# SuperClock_Core_PWR.net
KiCad netlist of a schematic drawn in Altium Designer
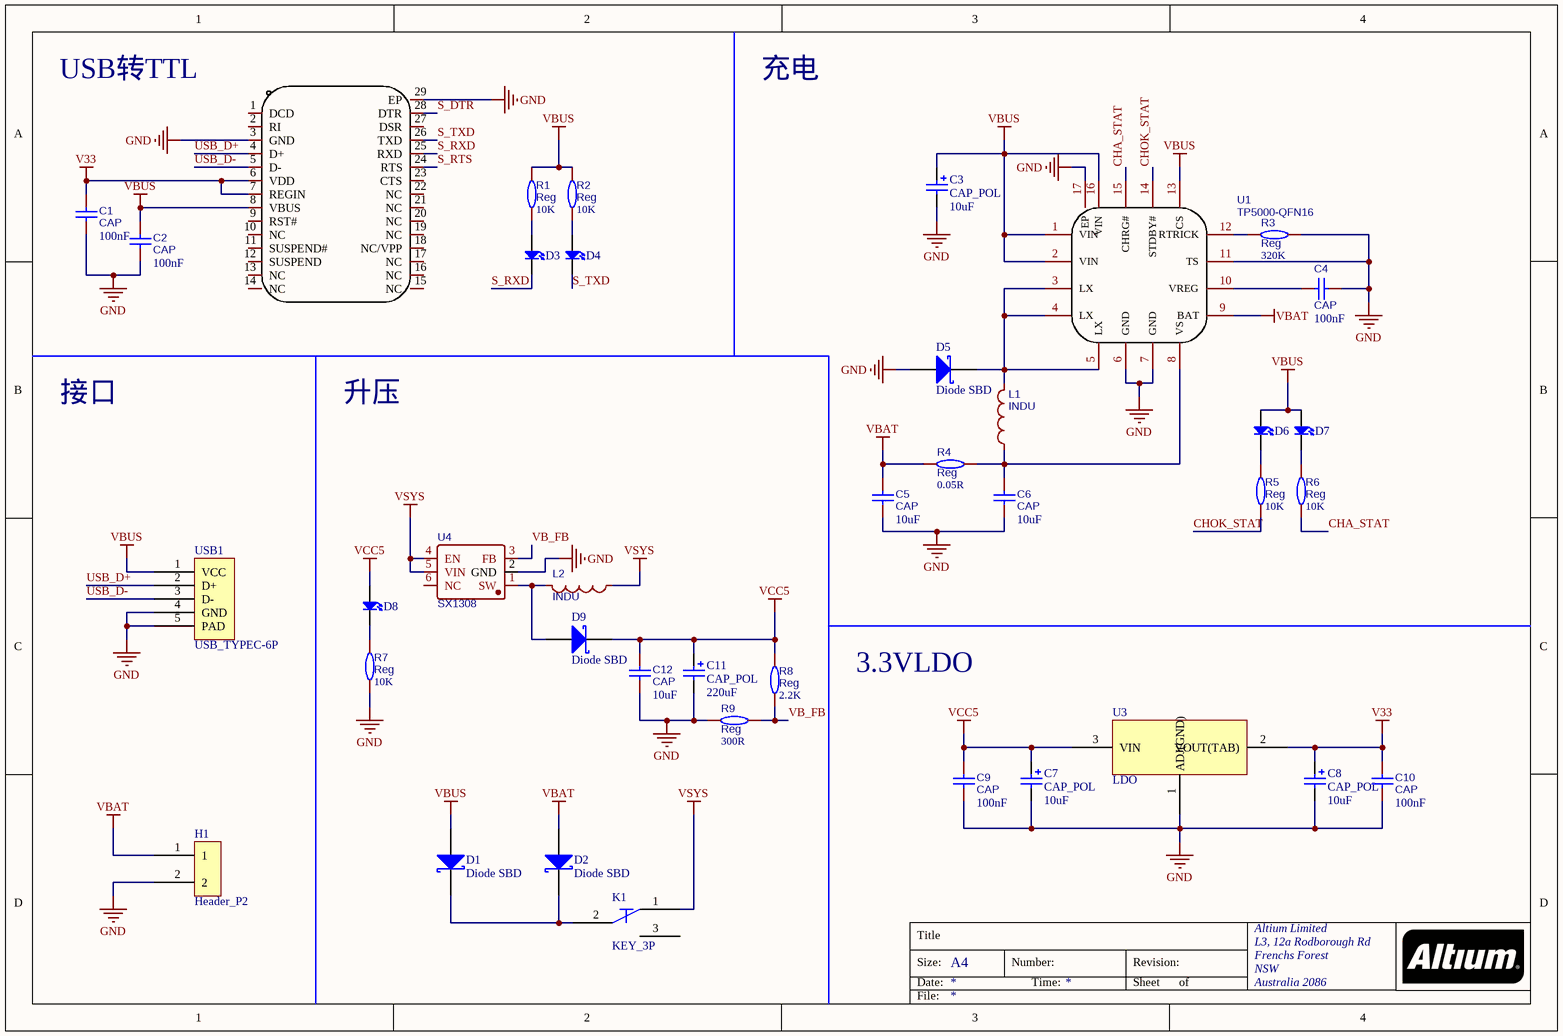
[diagram p0: SuperClock_Core_PWR.SchDoc]

(export (version "E")
  (design (tool "Eeschema 10.0.6"))
  (components
    (comp (ref "C1")
      (value "CAP")
      (footprint "C0603")
      (description "Cap")
      (fields
        (field (name "BOM_SUPPLIER PART") "C302008")
        (field (name "BOM_MANUFACTURER PART") "0603B103K101CT")
        (field (name "ALTIUM_VALUE") "100nF")
        (field (name "CONTRIBUTOR") "LCSC")
      )
      (libsource (lib "Levent_lib") (part "CAP"))
    )
    (comp (ref "C2")
      (value "CAP")
      (footprint "C0603")
      (description "Cap")
      (fields
        (field (name "BOM_SUPPLIER PART") "C302008")
        (field (name "BOM_MANUFACTURER PART") "0603B103K101CT")
        (field (name "ALTIUM_VALUE") "100nF")
        (field (name "CONTRIBUTOR") "LCSC")
      )
      (libsource (lib "Levent_lib") (part "CAP"))
    )
    (comp (ref "C3")
      (value "CAP_POL")
      (footprint "CP1206")
      (description "极性电容")
      (fields (field (name "ALTIUM_VALUE") "10uF"))
      (libsource (lib "Levent_lib") (part "CAP_POL"))
    )
    (comp (ref "C4")
      (value "CAP")
      (footprint "C0603")
      (description "Cap")
      (fields
        (field (name "BOM_SUPPLIER PART") "C302008")
        (field (name "BOM_MANUFACTURER PART") "0603B103K101CT")
        (field (name "ALTIUM_VALUE") "100nF")
        (field (name "CONTRIBUTOR") "LCSC")
      )
      (libsource (lib "Levent_lib") (part "CAP"))
    )
    (comp (ref "C5")
      (value "CAP")
      (footprint "C0603")
      (description "Cap")
      (fields
        (field (name "BOM_SUPPLIER PART") "C302008")
        (field (name "BOM_MANUFACTURER PART") "0603B103K101CT")
        (field (name "ALTIUM_VALUE") "10uF")
        (field (name "CONTRIBUTOR") "LCSC")
      )
      (libsource (lib "Levent_lib") (part "CAP"))
    )
    (comp (ref "C6")
      (value "CAP")
      (footprint "C0603")
      (description "Cap")
      (fields
        (field (name "BOM_SUPPLIER PART") "C302008")
        (field (name "BOM_MANUFACTURER PART") "0603B103K101CT")
        (field (name "ALTIUM_VALUE") "10uF")
        (field (name "CONTRIBUTOR") "LCSC")
      )
      (libsource (lib "Levent_lib") (part "CAP"))
    )
    (comp (ref "C7")
      (value "CAP_POL")
      (footprint "CP1206")
      (description "极性电容")
      (fields (field (name "ALTIUM_VALUE") "10uF"))
      (libsource (lib "Levent_lib") (part "CAP_POL"))
    )
    (comp (ref "C8")
      (value "CAP_POL")
      (footprint "CP1206")
      (description "极性电容")
      (fields (field (name "ALTIUM_VALUE") "10uF"))
      (libsource (lib "Levent_lib") (part "CAP_POL"))
    )
    (comp (ref "C9")
      (value "CAP")
      (footprint "C0603")
      (description "Cap")
      (fields
        (field (name "BOM_SUPPLIER PART") "C302008")
        (field (name "BOM_MANUFACTURER PART") "0603B103K101CT")
        (field (name "ALTIUM_VALUE") "100nF")
        (field (name "CONTRIBUTOR") "LCSC")
      )
      (libsource (lib "Levent_lib") (part "CAP"))
    )
    (comp (ref "C10")
      (value "CAP")
      (footprint "C0603")
      (description "Cap")
      (fields
        (field (name "BOM_SUPPLIER PART") "C302008")
        (field (name "BOM_MANUFACTURER PART") "0603B103K101CT")
        (field (name "ALTIUM_VALUE") "100nF")
        (field (name "CONTRIBUTOR") "LCSC")
      )
      (libsource (lib "Levent_lib") (part "CAP"))
    )
    (comp (ref "C11")
      (value "CAP_POL")
      (footprint "CAP_SMD_6.3mm")
      (description "极性电容")
      (fields (field (name "ALTIUM_VALUE") "220uF"))
      (libsource (lib "Levent_lib") (part "CAP_POL"))
    )
    (comp (ref "C12")
      (value "CAP")
      (footprint "C0603")
      (description "Cap")
      (fields
        (field (name "BOM_SUPPLIER PART") "C302008")
        (field (name "BOM_MANUFACTURER PART") "0603B103K101CT")
        (field (name "ALTIUM_VALUE") "10uF")
        (field (name "CONTRIBUTOR") "LCSC")
      )
      (libsource (lib "Levent_lib") (part "CAP"))
    )
    (comp (ref "D1")
      (value "Diode SBD")
      (footprint "SMA_L4.3")
      (description "Schottky Rectifier")
      (fields (field (name "PUBLISHER") "Altium Limited"))
      (libsource (lib "Levent_lib") (part "Diode SBD"))
    )
    (comp (ref "D2")
      (value "Diode SBD")
      (footprint "SMA_L4.3")
      (description "Schottky Rectifier")
      (fields (field (name "PUBLISHER") "Altium Limited"))
      (libsource (lib "Levent_lib") (part "Diode SBD"))
    )
    (comp (ref "D3")
      (value "LED")
      (footprint "LED0603")
      (fields (field (name "PUBLISHER") "Altium Limited"))
      (libsource (lib "Levent_lib") (part "LED0"))
    )
    (comp (ref "D4")
      (value "LED")
      (footprint "LED0603")
      (fields (field (name "PUBLISHER") "Altium Limited"))
      (libsource (lib "Levent_lib") (part "LED0"))
    )
    (comp (ref "D5")
      (value "Diode SBD")
      (footprint "SMA_L4.3")
      (description "Schottky Rectifier")
      (fields (field (name "PUBLISHER") "Altium Limited"))
      (libsource (lib "Levent_lib") (part "Diode SBD"))
    )
    (comp (ref "D6")
      (value "LED")
      (footprint "LED0603")
      (fields (field (name "PUBLISHER") "Altium Limited"))
      (libsource (lib "Levent_lib") (part "LED0"))
    )
    (comp (ref "D7")
      (value "LED")
      (footprint "LED0603")
      (fields (field (name "PUBLISHER") "Altium Limited"))
      (libsource (lib "Levent_lib") (part "LED0"))
    )
    (comp (ref "D8")
      (value "LED")
      (footprint "LED0603")
      (fields (field (name "PUBLISHER") "Altium Limited"))
      (libsource (lib "Levent_lib") (part "LED0"))
    )
    (comp (ref "D9")
      (value "Diode SBD")
      (footprint "SMA_L4.3")
      (description "Schottky Rectifier")
      (fields (field (name "PUBLISHER") "Altium Limited"))
      (libsource (lib "Levent_lib") (part "Diode SBD"))
    )
    (comp (ref "H1")
      (value "Header_P2")
      (footprint "PH_2Pin")
      (description "2Pin排针")
      (libsource (lib "Levent_lib") (part "Header_P2"))
    )
    (comp (ref "K1")
      (value "KEY_3P")
      (footprint "SWITCH_3P_2")
      (description "3Pin按键")
      (libsource (lib "Levent_lib") (part "KEY_3P"))
    )
    (comp (ref "L1")
      (value "INDU")
      (footprint "SMD_L7.1")
      (description "电感")
      (fields
        (field (name "BOM_SUPPLIER PART") "C182182")
        (field (name "BOM_MANUFACTURER PART") "SLO0630H150MTT")
        (field (name "CONTRIBUTOR") "LCSC")
      )
      (libsource (lib "Levent_lib") (part "IND"))
    )
    (comp (ref "L2")
      (value "INDU")
      (footprint "SMD_L7.1")
      (description "电感")
      (fields
        (field (name "BOM_SUPPLIER PART") "C182182")
        (field (name "BOM_MANUFACTURER PART") "SLO0630H150MTT")
        (field (name "CONTRIBUTOR") "LCSC")
      )
      (libsource (lib "Levent_lib") (part "IND"))
    )
    (comp (ref "R1")
      (value "Reg")
      (footprint "R0603")
      (description "电阻")
      (fields
        (field (name "BOM_SUPPLIER PART") "C465721")
        (field (name "BOM_MANUFACTURER PART") "AR03BTCX1002A")
        (field (name "ALTIUM_VALUE") "10K")
        (field (name "CONTRIBUTOR") "LCSC")
      )
      (libsource (lib "Levent_lib") (part "Res"))
    )
    (comp (ref "R2")
      (value "Reg")
      (footprint "R0603")
      (description "电阻")
      (fields
        (field (name "BOM_SUPPLIER PART") "C465721")
        (field (name "BOM_MANUFACTURER PART") "AR03BTCX1002A")
        (field (name "ALTIUM_VALUE") "10K")
        (field (name "CONTRIBUTOR") "LCSC")
      )
      (libsource (lib "Levent_lib") (part "Res"))
    )
    (comp (ref "R3")
      (value "Reg")
      (footprint "R0603")
      (description "电阻")
      (fields
        (field (name "BOM_SUPPLIER PART") "C465721")
        (field (name "BOM_MANUFACTURER PART") "AR03BTCX1002A")
        (field (name "ALTIUM_VALUE") "320K")
        (field (name "CONTRIBUTOR") "LCSC")
      )
      (libsource (lib "Levent_lib") (part "Res"))
    )
    (comp (ref "R4")
      (value "Reg")
      (footprint "R1206")
      (description "电阻")
      (fields
        (field (name "BOM_SUPPLIER PART") "C465721")
        (field (name "BOM_MANUFACTURER PART") "AR03BTCX1002A")
        (field (name "ALTIUM_VALUE") "0.05R")
        (field (name "CONTRIBUTOR") "LCSC")
      )
      (libsource (lib "Levent_lib") (part "Res"))
    )
    (comp (ref "R5")
      (value "Reg")
      (footprint "R0603")
      (description "电阻")
      (fields
        (field (name "BOM_SUPPLIER PART") "C465721")
        (field (name "BOM_MANUFACTURER PART") "AR03BTCX1002A")
        (field (name "ALTIUM_VALUE") "10K")
        (field (name "CONTRIBUTOR") "LCSC")
      )
      (libsource (lib "Levent_lib") (part "Res"))
    )
    (comp (ref "R6")
      (value "Reg")
      (footprint "R0603")
      (description "电阻")
      (fields
        (field (name "BOM_SUPPLIER PART") "C465721")
        (field (name "BOM_MANUFACTURER PART") "AR03BTCX1002A")
        (field (name "ALTIUM_VALUE") "10K")
        (field (name "CONTRIBUTOR") "LCSC")
      )
      (libsource (lib "Levent_lib") (part "Res"))
    )
    (comp (ref "R7")
      (value "Reg")
      (footprint "R0603")
      (description "电阻")
      (fields
        (field (name "BOM_SUPPLIER PART") "C465721")
        (field (name "BOM_MANUFACTURER PART") "AR03BTCX1002A")
        (field (name "ALTIUM_VALUE") "10K")
        (field (name "CONTRIBUTOR") "LCSC")
      )
      (libsource (lib "Levent_lib") (part "Res"))
    )
    (comp (ref "R8")
      (value "Reg")
      (footprint "R0603")
      (description "电阻")
      (fields
        (field (name "BOM_SUPPLIER PART") "C465721")
        (field (name "BOM_MANUFACTURER PART") "AR03BTCX1002A")
        (field (name "ALTIUM_VALUE") "2.2K")
        (field (name "CONTRIBUTOR") "LCSC")
      )
      (libsource (lib "Levent_lib") (part "Res"))
    )
    (comp (ref "R9")
      (value "Reg")
      (footprint "R0603")
      (description "电阻")
      (fields
        (field (name "BOM_SUPPLIER PART") "C465721")
        (field (name "BOM_MANUFACTURER PART") "AR03BTCX1002A")
        (field (name "ALTIUM_VALUE") "300R")
        (field (name "CONTRIBUTOR") "LCSC")
      )
      (libsource (lib "Levent_lib") (part "Res"))
    )
    (comp (ref "U1")
      (value "TP5000-QFN16")
      (footprint "QFN-16_L4.0-W4.0-P0.65-BL-EP2.2")
      (fields (field (name "BOM_SUPPLIER PART") "C51699"))
      (libsource (lib "Levent_lib") (part "TP5000-QFN16"))
    )
    (comp (ref "U2")
      (value "CP2102-GM")
      (footprint "QFN-28")
      (description "CP2102USB转串口")
      (fields (field (name "MANUFACTURER") "SILICON LABS(芯科)"))
      (libsource (lib "Levent_lib") (part "CP2102-GM"))
    )
    (comp (ref "U3") (value "LDO") (footprint "SOT-223") (libsource (lib "Levent_lib") (part "AMS1117")))
    (comp (ref "U4")
      (value "SX1308")
      (footprint "SOT-23-6")
      (description "升压PWM")
      (fields (field (name "BOM_SUPPLIER PART") "C78162"))
      (libsource (lib "Levent_lib") (part "SX1308"))
    )
    (comp (ref "USB1")
      (value "USB_TYPEC-6P")
      (footprint "USB_TYPEC")
      (libsource (lib "Levent_lib") (part "USB_TYPEC"))
    )
  )
  (nets
    (net (code "1") (name "/CHA_STAT") (class "Default")
      (node (ref "R6") (pin "1") (pinfunction "1_1") (pintype "passive"))
      (node (ref "U1") (pin "15") (pinfunction "CHRG#_15") (pintype "passive"))
    )
    (net (code "2") (name "/CHOK_STAT") (class "Default")
      (node (ref "R5") (pin "1") (pinfunction "1_1") (pintype "passive"))
      (node (ref "U1") (pin "14") (pinfunction "STDBY#_14") (pintype "passive"))
    )
    (net (code "3") (name "/S_DTR") (class "Default")
      (node (ref "U2") (pin "28") (pinfunction "DTR_28") (pintype "passive"))
    )
    (net (code "4") (name "/S_RTS") (class "Default")
      (node (ref "U2") (pin "24") (pinfunction "RTS_24") (pintype "passive"))
    )
    (net (code "5") (name "/S_RXD") (class "Default")
      (node (ref "D3") (pin "1") (pinfunction "K_1") (pintype "passive"))
      (node (ref "U2") (pin "25") (pinfunction "RXD_25") (pintype "passive"))
    )
    (net (code "6") (name "/S_TXD") (class "Default")
      (node (ref "D4") (pin "1") (pinfunction "K_1") (pintype "passive"))
      (node (ref "U2") (pin "26") (pinfunction "TXD_26") (pintype "passive"))
    )
    (net (code "7") (name "/USB_D+") (class "Default")
      (node (ref "U2") (pin "4") (pinfunction "D+_4") (pintype "passive"))
      (node (ref "USB1") (pin "2") (pinfunction "D+_2") (pintype "passive"))
    )
    (net (code "8") (name "/USB_D-") (class "Default")
      (node (ref "U2") (pin "5") (pinfunction "D-_5") (pintype "passive"))
      (node (ref "USB1") (pin "3") (pinfunction "D-_3") (pintype "passive"))
    )
    (net (code "9") (name "/VB_FB") (class "Default")
      (node (ref "R8") (pin "1") (pinfunction "1_1") (pintype "passive"))
      (node (ref "R9") (pin "1") (pinfunction "1_1") (pintype "passive"))
      (node (ref "U4") (pin "3") (pinfunction "FB_3") (pintype "passive"))
    )
    (net (code "10") (name "GND") (class "Default")
      (node (ref "C1") (pin "2") (pinfunction "2_2") (pintype "passive"))
      (node (ref "C10") (pin "2") (pinfunction "2_2") (pintype "passive"))
      (node (ref "C11") (pin "2") (pinfunction "2_2") (pintype "passive"))
      (node (ref "C12") (pin "2") (pinfunction "2_2") (pintype "passive"))
      (node (ref "C2") (pin "2") (pinfunction "2_2") (pintype "passive"))
      (node (ref "C3") (pin "2") (pinfunction "2_2") (pintype "passive"))
      (node (ref "C4") (pin "2") (pinfunction "2_2") (pintype "passive"))
      (node (ref "C5") (pin "2") (pinfunction "2_2") (pintype "passive"))
      (node (ref "C6") (pin "2") (pinfunction "2_2") (pintype "passive"))
      (node (ref "C7") (pin "2") (pinfunction "2_2") (pintype "passive"))
      (node (ref "C8") (pin "2") (pinfunction "2_2") (pintype "passive"))
      (node (ref "C9") (pin "2") (pinfunction "2_2") (pintype "passive"))
      (node (ref "D5") (pin "2") (pinfunction "A_2") (pintype "passive"))
      (node (ref "H1") (pin "2") (pinfunction "2_2") (pintype "passive"))
      (node (ref "R3") (pin "2") (pinfunction "2_2") (pintype "passive"))
      (node (ref "R7") (pin "1") (pinfunction "1_1") (pintype "passive"))
      (node (ref "R9") (pin "2") (pinfunction "2_2") (pintype "passive"))
      (node (ref "U1") (pin "11") (pinfunction "TS_11") (pintype "passive"))
      (node (ref "U1") (pin "17") (pinfunction "EP_17") (pintype "passive"))
      (node (ref "U1") (pin "6") (pinfunction "GND_6") (pintype "passive"))
      (node (ref "U1") (pin "7") (pinfunction "GND_7") (pintype "passive"))
      (node (ref "U2") (pin "29") (pinfunction "EP_29") (pintype "passive"))
      (node (ref "U2") (pin "3") (pinfunction "GND_3") (pintype "passive"))
      (node (ref "U3") (pin "1") (pinfunction "ADJ(GND)_1") (pintype "passive"))
      (node (ref "U4") (pin "2") (pinfunction "GND_2") (pintype "passive"))
      (node (ref "USB1") (pin "4") (pinfunction "GND_4") (pintype "passive"))
      (node (ref "USB1") (pin "5") (pinfunction "PAD_5") (pintype "passive"))
    )
    (net (code "11") (name "Net-(D1-K)") (class "Default")
      (node (ref "D1") (pin "1") (pinfunction "K_1") (pintype "passive"))
      (node (ref "D2") (pin "1") (pinfunction "K_1") (pintype "passive"))
      (node (ref "K1") (pin "2") (pinfunction "2_2") (pintype "passive"))
    )
    (net (code "12") (name "Net-(D3-A)") (class "Default")
      (node (ref "D3") (pin "2") (pinfunction "A_2") (pintype "passive"))
      (node (ref "R1") (pin "1") (pinfunction "1_1") (pintype "passive"))
    )
    (net (code "13") (name "Net-(D4-A)") (class "Default")
      (node (ref "D4") (pin "2") (pinfunction "A_2") (pintype "passive"))
      (node (ref "R2") (pin "1") (pinfunction "1_1") (pintype "passive"))
    )
    (net (code "14") (name "Net-(D5-K)") (class "Default")
      (node (ref "D5") (pin "1") (pinfunction "K_1") (pintype "passive"))
      (node (ref "L1") (pin "2") (pinfunction "2_2") (pintype "passive"))
      (node (ref "U1") (pin "3") (pinfunction "LX_3") (pintype "passive"))
      (node (ref "U1") (pin "4") (pinfunction "LX_4") (pintype "passive"))
      (node (ref "U1") (pin "5") (pinfunction "LX_5") (pintype "passive"))
    )
    (net (code "15") (name "Net-(D6-K)") (class "Default")
      (node (ref "D6") (pin "1") (pinfunction "K_1") (pintype "passive"))
      (node (ref "R5") (pin "2") (pinfunction "2_2") (pintype "passive"))
    )
    (net (code "16") (name "Net-(D7-K)") (class "Default")
      (node (ref "D7") (pin "1") (pinfunction "K_1") (pintype "passive"))
      (node (ref "R6") (pin "2") (pinfunction "2_2") (pintype "passive"))
    )
    (net (code "17") (name "Net-(D8-K)") (class "Default")
      (node (ref "D8") (pin "1") (pinfunction "K_1") (pintype "passive"))
      (node (ref "R7") (pin "2") (pinfunction "2_2") (pintype "passive"))
    )
    (net (code "18") (name "Net-(D9-A)") (class "Default")
      (node (ref "D9") (pin "2") (pinfunction "A_2") (pintype "passive"))
      (node (ref "L2") (pin "2") (pinfunction "2_2") (pintype "passive"))
      (node (ref "U4") (pin "1") (pinfunction "SW_1") (pintype "passive"))
    )
    (net (code "19") (name "Net-(U1-RTRICK)") (class "Default")
      (node (ref "R3") (pin "1") (pinfunction "1_1") (pintype "passive"))
      (node (ref "U1") (pin "12") (pinfunction "RTRICK_12") (pintype "passive"))
    )
    (net (code "20") (name "Net-(U1-VREG)") (class "Default")
      (node (ref "C4") (pin "1") (pinfunction "1_1") (pintype "passive"))
      (node (ref "U1") (pin "10") (pinfunction "VREG_10") (pintype "passive"))
    )
    (net (code "21") (name "Net-(U1-VS)") (class "Default")
      (node (ref "C6") (pin "1") (pinfunction "1_1") (pintype "passive"))
      (node (ref "L1") (pin "1") (pinfunction "1_1") (pintype "passive"))
      (node (ref "R4") (pin "2") (pinfunction "2_2") (pintype "passive"))
      (node (ref "U1") (pin "8") (pinfunction "VS_8") (pintype "passive"))
    )
    (net (code "22") (name "V33") (class "Default")
      (node (ref "C1") (pin "1") (pinfunction "1_1") (pintype "passive"))
      (node (ref "C10") (pin "1") (pinfunction "1_1") (pintype "passive"))
      (node (ref "C8") (pin "1") (pinfunction "1_1") (pintype "passive"))
      (node (ref "U2") (pin "6") (pinfunction "VDD_6") (pintype "passive"))
      (node (ref "U2") (pin "7") (pinfunction "REGIN_7") (pintype "passive"))
      (node (ref "U3") (pin "2") (pinfunction "VOUT(TAB)_2") (pintype "passive"))
    )
    (net (code "23") (name "VBAT") (class "Default")
      (node (ref "C5") (pin "1") (pinfunction "1_1") (pintype "passive"))
      (node (ref "D2") (pin "2") (pinfunction "A_2") (pintype "passive"))
      (node (ref "H1") (pin "1") (pinfunction "1_1") (pintype "passive"))
      (node (ref "R4") (pin "1") (pinfunction "1_1") (pintype "passive"))
      (node (ref "U1") (pin "9") (pinfunction "BAT_9") (pintype "passive"))
    )
    (net (code "24") (name "VBUS") (class "Default")
      (node (ref "C2") (pin "1") (pinfunction "1_1") (pintype "passive"))
      (node (ref "C3") (pin "1") (pinfunction "1_1") (pintype "passive"))
      (node (ref "D1") (pin "2") (pinfunction "A_2") (pintype "passive"))
      (node (ref "D6") (pin "2") (pinfunction "A_2") (pintype "passive"))
      (node (ref "D7") (pin "2") (pinfunction "A_2") (pintype "passive"))
      (node (ref "R1") (pin "2") (pinfunction "2_2") (pintype "passive"))
      (node (ref "R2") (pin "2") (pinfunction "2_2") (pintype "passive"))
      (node (ref "U1") (pin "1") (pinfunction "VIN_1") (pintype "passive"))
      (node (ref "U1") (pin "13") (pinfunction "CS_13") (pintype "passive"))
      (node (ref "U1") (pin "16") (pinfunction "VIN_16") (pintype "passive"))
      (node (ref "U1") (pin "2") (pinfunction "VIN_2") (pintype "passive"))
      (node (ref "U2") (pin "8") (pinfunction "VBUS_8") (pintype "passive"))
      (node (ref "USB1") (pin "1") (pinfunction "VCC_1") (pintype "passive"))
    )
    (net (code "25") (name "VCC5") (class "Default")
      (node (ref "C11") (pin "1") (pinfunction "1_1") (pintype "passive"))
      (node (ref "C12") (pin "1") (pinfunction "1_1") (pintype "passive"))
      (node (ref "C7") (pin "1") (pinfunction "1_1") (pintype "passive"))
      (node (ref "C9") (pin "1") (pinfunction "1_1") (pintype "passive"))
      (node (ref "D8") (pin "2") (pinfunction "A_2") (pintype "passive"))
      (node (ref "D9") (pin "1") (pinfunction "K_1") (pintype "passive"))
      (node (ref "R8") (pin "2") (pinfunction "2_2") (pintype "passive"))
      (node (ref "U3") (pin "3") (pinfunction "VIN_3") (pintype "passive"))
    )
    (net (code "26") (name "VSYS") (class "Default")
      (node (ref "K1") (pin "1") (pinfunction "1_1") (pintype "passive"))
      (node (ref "L2") (pin "1") (pinfunction "1_1") (pintype "passive"))
      (node (ref "U4") (pin "4") (pinfunction "EN_4") (pintype "passive"))
      (node (ref "U4") (pin "5") (pinfunction "VIN_5") (pintype "passive"))
    )
    (net (code "27") (name "unconnected-(K1-Pad3)") (class "Default")
      (node (ref "K1") (pin "3") (pinfunction "3_3") (pintype "passive"))
    )
    (net (code "28") (name "unconnected-(U2-CTS-Pad23)") (class "Default")
      (node (ref "U2") (pin "23") (pinfunction "CTS_23") (pintype "passive"))
    )
    (net (code "29") (name "unconnected-(U2-DCD-Pad1)") (class "Default")
      (node (ref "U2") (pin "1") (pinfunction "DCD_1") (pintype "passive"))
    )
    (net (code "30") (name "unconnected-(U2-DSR-Pad27)") (class "Default")
      (node (ref "U2") (pin "27") (pinfunction "DSR_27") (pintype "passive"))
    )
    (net (code "31") (name "unconnected-(U2-NC-Pad10)") (class "Default")
      (node (ref "U2") (pin "10") (pinfunction "NC_10") (pintype "passive"))
    )
    (net (code "32") (name "unconnected-(U2-NC-Pad13)") (class "Default")
      (node (ref "U2") (pin "13") (pinfunction "NC_13") (pintype "passive"))
    )
    (net (code "33") (name "unconnected-(U2-NC-Pad14)") (class "Default")
      (node (ref "U2") (pin "14") (pinfunction "NC_14") (pintype "passive"))
    )
    (net (code "34") (name "unconnected-(U2-NC-Pad15)") (class "Default")
      (node (ref "U2") (pin "15") (pinfunction "NC_15") (pintype "passive"))
    )
    (net (code "35") (name "unconnected-(U2-NC-Pad16)") (class "Default")
      (node (ref "U2") (pin "16") (pinfunction "NC_16") (pintype "passive"))
    )
    (net (code "36") (name "unconnected-(U2-NC-Pad17)") (class "Default")
      (node (ref "U2") (pin "17") (pinfunction "NC_17") (pintype "passive"))
    )
    (net (code "37") (name "unconnected-(U2-NC-Pad19)") (class "Default")
      (node (ref "U2") (pin "19") (pinfunction "NC_19") (pintype "passive"))
    )
    (net (code "38") (name "unconnected-(U2-NC-Pad20)") (class "Default")
      (node (ref "U2") (pin "20") (pinfunction "NC_20") (pintype "passive"))
    )
    (net (code "39") (name "unconnected-(U2-NC-Pad21)") (class "Default")
      (node (ref "U2") (pin "21") (pinfunction "NC_21") (pintype "passive"))
    )
    (net (code "40") (name "unconnected-(U2-NC-Pad22)") (class "Default")
      (node (ref "U2") (pin "22") (pinfunction "NC_22") (pintype "passive"))
    )
    (net (code "41") (name "unconnected-(U2-NC{slash}VPP-Pad18)") (class "Default")
      (node (ref "U2") (pin "18") (pinfunction "NC/VPP_18") (pintype "passive"))
    )
    (net (code "42") (name "unconnected-(U2-RI-Pad2)") (class "Default")
      (node (ref "U2") (pin "2") (pinfunction "RI_2") (pintype "passive"))
    )
    (net (code "43") (name "unconnected-(U2-RST#-Pad9)") (class "Default")
      (node (ref "U2") (pin "9") (pinfunction "RST#_9") (pintype "passive"))
    )
    (net (code "44") (name "unconnected-(U2-SUSPEND#-Pad11)") (class "Default")
      (node (ref "U2") (pin "11") (pinfunction "SUSPEND#_11") (pintype "passive"))
    )
    (net (code "45") (name "unconnected-(U2-SUSPEND-Pad12)") (class "Default")
      (node (ref "U2") (pin "12") (pinfunction "SUSPEND_12") (pintype "passive"))
    )
    (net (code "46") (name "unconnected-(U4-NC-Pad6)") (class "Default")
      (node (ref "U4") (pin "6") (pinfunction "NC_6") (pintype "passive"))
    )
  )
)
